# microcontroller.net
KiCad netlist of a schematic drawn in Altium Designer
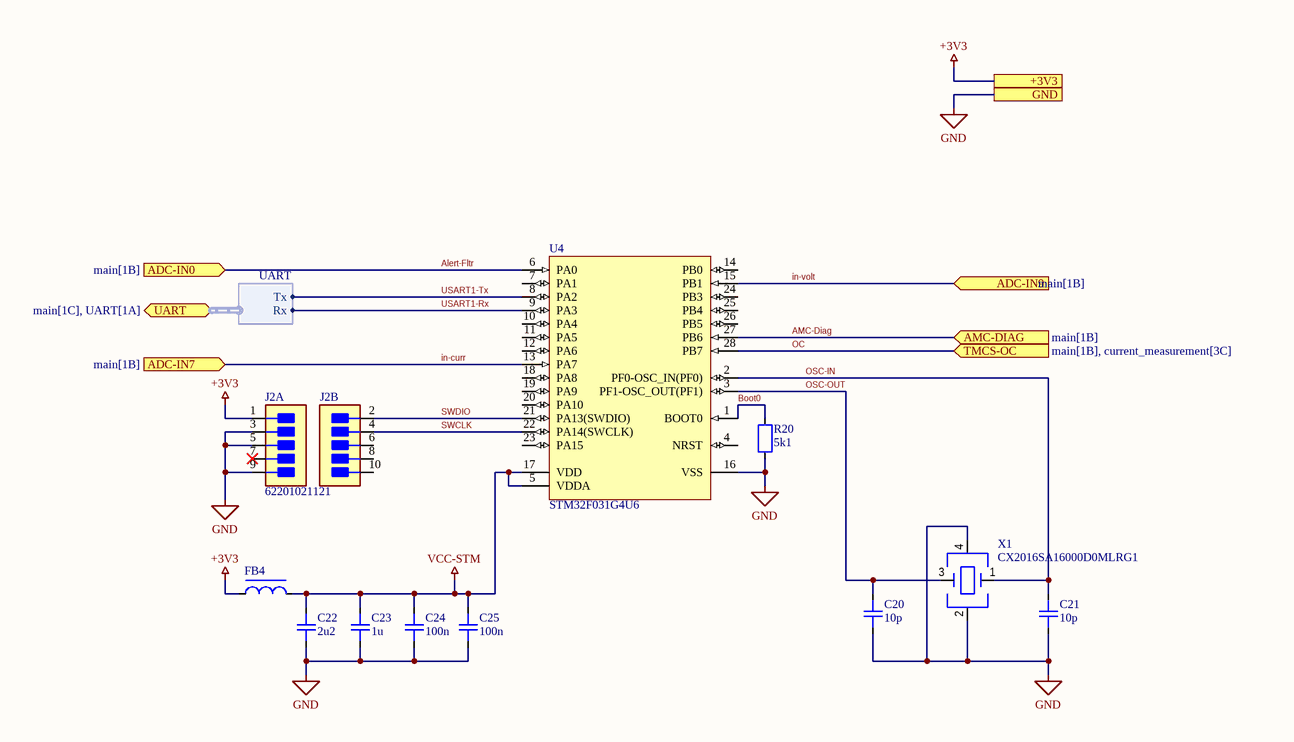
[diagram p0: microcontroller.SchDoc]

(export (version "E")
  (design (tool "Eeschema 10.0.6"))
  (components
    (comp (ref "C20")
      (value "10p")
      (footprint "CAP0603")
      (libsource (lib "Integrated_Library_main") (part "Capacitor"))
    )
    (comp (ref "C21")
      (value "10p")
      (footprint "CAP0603")
      (libsource (lib "Integrated_Library_main") (part "Capacitor"))
    )
    (comp (ref "C22")
      (value "2u2")
      (footprint "CAP0603")
      (libsource (lib "Integrated_Library_main") (part "Capacitor"))
    )
    (comp (ref "C23")
      (value "1u")
      (footprint "CAP0603")
      (libsource (lib "Integrated_Library_main") (part "Capacitor"))
    )
    (comp (ref "C24")
      (value "100n")
      (footprint "CAP0204")
      (libsource (lib "Integrated_Library_main") (part "Capacitor"))
    )
    (comp (ref "C25")
      (value "100n")
      (footprint "CAP0204")
      (libsource (lib "Integrated_Library_main") (part "Capacitor"))
    )
    (comp (ref "FB4")
      (value "*")
      (footprint "FB0402")
      (libsource (lib "Integrated_Library_main") (part "Ferrite Bead"))
    )
    (comp (ref "J2")
      (value "62201021121")
      (footprint "62201021121")
      (description "CONN HEADER VERT 10POS 1.27MM")
      (libsource (lib "Integrated_Library_main") (part "62201021121"))
    )
    (comp (ref "R20")
      (value "5k1")
      (footprint "RES0603")
      (libsource (lib "Integrated_Library_main") (part "Resistor"))
    )
    (comp (ref "U4")
      (value "STM32F031G4U6")
      (footprint "STM-UFQFPN28_V")
      (libsource (lib "Integrated_Library_main") (part "STM32F031G4U6"))
    )
    (comp (ref "X1")
      (value "CX2016SA16000D0MLRG1")
      (footprint "CX2016")
      (description "Crystals 2.0mm x 1.6mm Crystal 16MHz 8pF +/-40ppm")
      (libsource (lib "Integrated_Library_main") (part "CX2016SA16000D0MLRG1"))
    )
  )
  (nets
    (net (code "2") (name "+3V3") (class "Default")
      (node (ref "FB4") (pin "1") (pintype "passive"))
      (node (ref "J2") (pin "1") (pinfunction "1_1") (pintype "passive"))
    )
    (net (code "3") (name "/AMC-Diag") (class "Default")
      (node (ref "U4") (pin "27") (pinfunction "PB6_27") (pintype "input"))
    )
    (net (code "4") (name "/Alert-Fltr") (class "Default")
      (node (ref "U4") (pin "6") (pinfunction "PA0_6") (pintype "input"))
    )
    (net (code "5") (name "/Boot0") (class "Default")
      (node (ref "R20") (pin "1") (pintype "passive"))
      (node (ref "U4") (pin "1") (pinfunction "BOOT0_1") (pintype "input"))
    )
    (net (code "6") (name "/OC") (class "Default")
      (node (ref "U4") (pin "28") (pinfunction "PB7_28") (pintype "input"))
    )
    (net (code "7") (name "/OSC-IN") (class "Default")
      (node (ref "C21") (pin "1") (pintype "passive"))
      (node (ref "U4") (pin "2") (pinfunction "PF0-OSC_IN(PF0)_2") (pintype "bidirectional"))
      (node (ref "X1") (pin "1") (pinfunction "1_1") (pintype "passive"))
    )
    (net (code "8") (name "/OSC-OUT") (class "Default")
      (node (ref "C20") (pin "1") (pintype "passive"))
      (node (ref "U4") (pin "3") (pinfunction "PF1-OSC_OUT(PF1)_3") (pintype "bidirectional"))
      (node (ref "X1") (pin "3") (pinfunction "3_3") (pintype "passive"))
    )
    (net (code "9") (name "/SWCLK") (class "Default")
      (node (ref "J2") (pin "4") (pinfunction "4_4") (pintype "passive"))
      (node (ref "U4") (pin "22") (pinfunction "PA14(SWCLK)_22") (pintype "bidirectional"))
    )
    (net (code "10") (name "/SWDIO") (class "Default")
      (node (ref "J2") (pin "2") (pinfunction "2_2") (pintype "passive"))
      (node (ref "U4") (pin "21") (pinfunction "PA13(SWDIO)_21") (pintype "bidirectional"))
    )
    (net (code "11") (name "/USART1-Rx") (class "Default")
      (node (ref "U4") (pin "9") (pinfunction "PA3_9") (pintype "bidirectional"))
    )
    (net (code "12") (name "/USART1-Tx") (class "Default")
      (node (ref "U4") (pin "8") (pinfunction "PA2_8") (pintype "bidirectional"))
    )
    (net (code "13") (name "/in-curr") (class "Default")
      (node (ref "U4") (pin "13") (pinfunction "PA7_13") (pintype "input"))
    )
    (net (code "14") (name "/in-volt") (class "Default")
      (node (ref "U4") (pin "15") (pinfunction "PB1_15") (pintype "input"))
    )
    (net (code "16") (name "GND") (class "Default")
      (node (ref "C20") (pin "2") (pintype "passive"))
      (node (ref "C21") (pin "2") (pintype "passive"))
      (node (ref "C22") (pin "2") (pintype "passive"))
      (node (ref "C23") (pin "2") (pintype "passive"))
      (node (ref "C24") (pin "2") (pintype "passive"))
      (node (ref "C25") (pin "2") (pintype "passive"))
      (node (ref "J2") (pin "3") (pinfunction "3_3") (pintype "passive"))
      (node (ref "J2") (pin "5") (pinfunction "5_5") (pintype "passive"))
      (node (ref "J2") (pin "9") (pinfunction "9_9") (pintype "passive"))
      (node (ref "R20") (pin "2") (pintype "passive"))
      (node (ref "U4") (pin "16") (pinfunction "VSS_16") (pintype "power_in"))
      (node (ref "X1") (pin "2") (pinfunction "2_2") (pintype "passive"))
      (node (ref "X1") (pin "4") (pinfunction "4_4") (pintype "passive"))
    )
    (net (code "17") (name "VCC-STM") (class "Default")
      (node (ref "C22") (pin "1") (pintype "passive"))
      (node (ref "C23") (pin "1") (pintype "passive"))
      (node (ref "C24") (pin "1") (pintype "passive"))
      (node (ref "C25") (pin "1") (pintype "passive"))
      (node (ref "FB4") (pin "2") (pintype "passive"))
      (node (ref "U4") (pin "17") (pinfunction "VDD_17") (pintype "power_in"))
      (node (ref "U4") (pin "5") (pinfunction "VDDA_5") (pintype "power_in"))
    )
    (net (code "18") (name "unconnected-(J2-Pad6)") (class "Default")
      (node (ref "J2") (pin "6") (pinfunction "6_6") (pintype "passive"))
    )
    (net (code "19") (name "unconnected-(J2-Pad7)") (class "Default")
      (node (ref "J2") (pin "7") (pinfunction "7_7") (pintype "passive+no_connect"))
    )
    (net (code "20") (name "unconnected-(J2-Pad8)") (class "Default")
      (node (ref "J2") (pin "8") (pinfunction "8_8") (pintype "passive"))
    )
    (net (code "21") (name "unconnected-(J2-Pad10)") (class "Default")
      (node (ref "J2") (pin "10") (pinfunction "10_10") (pintype "passive"))
    )
    (net (code "22") (name "unconnected-(U4-NRST-Pad4)") (class "Default")
      (node (ref "U4") (pin "4") (pinfunction "NRST_4") (pintype "bidirectional"))
    )
    (net (code "23") (name "unconnected-(U4-PA1-Pad7)") (class "Default")
      (node (ref "U4") (pin "7") (pinfunction "PA1_7") (pintype "bidirectional"))
    )
    (net (code "24") (name "unconnected-(U4-PA4-Pad10)") (class "Default")
      (node (ref "U4") (pin "10") (pinfunction "PA4_10") (pintype "bidirectional"))
    )
    (net (code "25") (name "unconnected-(U4-PA5-Pad11)") (class "Default")
      (node (ref "U4") (pin "11") (pinfunction "PA5_11") (pintype "bidirectional"))
    )
    (net (code "26") (name "unconnected-(U4-PA6-Pad12)") (class "Default")
      (node (ref "U4") (pin "12") (pinfunction "PA6_12") (pintype "bidirectional"))
    )
    (net (code "27") (name "unconnected-(U4-PA8-Pad18)") (class "Default")
      (node (ref "U4") (pin "18") (pinfunction "PA8_18") (pintype "bidirectional"))
    )
    (net (code "28") (name "unconnected-(U4-PA9-Pad19)") (class "Default")
      (node (ref "U4") (pin "19") (pinfunction "PA9_19") (pintype "bidirectional"))
    )
    (net (code "29") (name "unconnected-(U4-PA10-Pad20)") (class "Default")
      (node (ref "U4") (pin "20") (pinfunction "PA10_20") (pintype "bidirectional"))
    )
    (net (code "30") (name "unconnected-(U4-PA15-Pad23)") (class "Default")
      (node (ref "U4") (pin "23") (pinfunction "PA15_23") (pintype "bidirectional"))
    )
    (net (code "31") (name "unconnected-(U4-PB0-Pad14)") (class "Default")
      (node (ref "U4") (pin "14") (pinfunction "PB0_14") (pintype "bidirectional"))
    )
    (net (code "32") (name "unconnected-(U4-PB3-Pad24)") (class "Default")
      (node (ref "U4") (pin "24") (pinfunction "PB3_24") (pintype "bidirectional"))
    )
    (net (code "33") (name "unconnected-(U4-PB4-Pad25)") (class "Default")
      (node (ref "U4") (pin "25") (pinfunction "PB4_25") (pintype "bidirectional"))
    )
    (net (code "34") (name "unconnected-(U4-PB5-Pad26)") (class "Default")
      (node (ref "U4") (pin "26") (pinfunction "PB5_26") (pintype "bidirectional"))
    )
  )
)
